# LNA_Testboard.net
KiCad netlist of a schematic drawn in Altium Designer
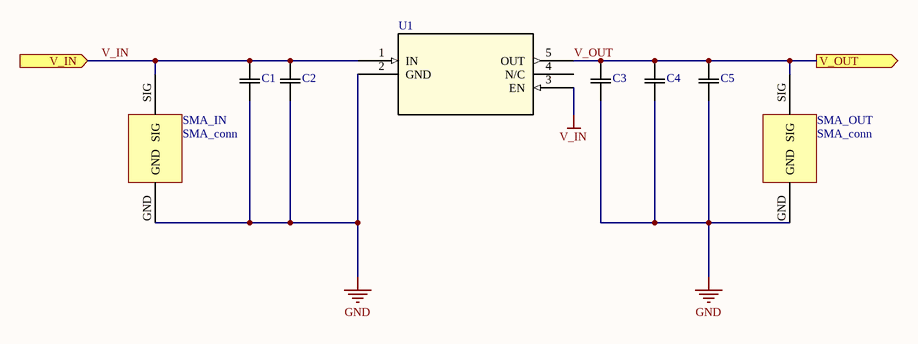
[diagram p0: LNA_Testboard.SchDoc]

(export (version "E")
  (design (tool "Eeschema 10.0.6"))
  (components
    (comp (ref "C1")
      (value "~")
      (footprint "0402Capacitor_Yageo:YAG_CC0402")
      (description "No Description Available")
      (fields
        (field (name "MANUFACTURER_PART_NUMBER") "C0201C270J3GACTU")
        (field (name "COPYRIGHT") "Copyright (C) 2018 Accelerated Designs. All rights reserved")
      )
      (libsource (lib "0201Capacitor_Yageo") (part "C0201C270J3GACTU"))
    )
    (comp (ref "C2")
      (value "~")
      (footprint "0402Capacitor_Yageo:YAG_CC0402")
      (description "No Description Available")
      (fields
        (field (name "MANUFACTURER_PART_NUMBER") "C0201C270J3GACTU")
        (field (name "COPYRIGHT") "Copyright (C) 2018 Accelerated Designs. All rights reserved")
      )
      (libsource (lib "0201Capacitor_Yageo") (part "C0201C270J3GACTU"))
    )
    (comp (ref "C3")
      (value "~")
      (footprint "0402Capacitor_Yageo:YAG_CC0402")
      (description "No Description Available")
      (fields
        (field (name "MANUFACTURER_PART_NUMBER") "C0201C270J3GACTU")
        (field (name "COPYRIGHT") "Copyright (C) 2018 Accelerated Designs. All rights reserved")
      )
      (libsource (lib "0201Capacitor_Yageo") (part "C0201C270J3GACTU"))
    )
    (comp (ref "C4")
      (value "~")
      (footprint "0402Capacitor_Yageo:YAG_CC0402")
      (description "No Description Available")
      (fields
        (field (name "MANUFACTURER_PART_NUMBER") "C0201C270J3GACTU")
        (field (name "COPYRIGHT") "Copyright (C) 2018 Accelerated Designs. All rights reserved")
      )
      (libsource (lib "0201Capacitor_Yageo") (part "C0201C270J3GACTU"))
    )
    (comp (ref "C5")
      (value "~")
      (footprint "0402Capacitor_Yageo:YAG_CC0402")
      (description "No Description Available")
      (fields
        (field (name "MANUFACTURER_PART_NUMBER") "C0201C270J3GACTU")
        (field (name "COPYRIGHT") "Copyright (C) 2018 Accelerated Designs. All rights reserved")
      )
      (libsource (lib "0201Capacitor_Yageo") (part "C0201C270J3GACTU"))
    )
    (comp (ref "SMA_IN")
      (value "SMA_conn")
      (footprint "SMA_conn")
      (libsource (lib "SMA_conn") (part "SMA_conn"))
    )
    (comp (ref "SMA_OUT")
      (value "SMA_conn")
      (footprint "SMA_conn")
      (libsource (lib "SMA_conn") (part "SMA_conn"))
    )
    (comp (ref "U1")
      (value "~")
      (footprint "TI_LDO_3V3_SOT325:DBV5")
      (description "No Description Available")
      (fields
        (field (name "MANUFACTURER_PART_NUMBER") "LP5907MFX-3.3/NOPB")
        (field (name "COPYRIGHT") "Copyright (C) 2018 Accelerated Designs. All rights reserved")
      )
      (libsource (lib "TI_LDO_3V3_SOT325") (part "LP5907MFX-3.3/NO"))
    )
  )
  (nets
    (net (code "1") (name "/V_OUT") (class "Default")
      (node (ref "C3") (pin "1") (pinfunction "1_1") (pintype "passive"))
      (node (ref "C4") (pin "1") (pinfunction "1_1") (pintype "passive"))
      (node (ref "C5") (pin "1") (pinfunction "1_1") (pintype "passive"))
      (node (ref "SMA_OUT") (pin "SIG") (pinfunction "SIG_SIG") (pintype "passive"))
      (node (ref "U1") (pin "5") (pinfunction "OUT_5") (pintype "output"))
    )
    (net (code "2") (name "GND") (class "Default")
      (node (ref "C1") (pin "2") (pinfunction "2_2") (pintype "passive"))
      (node (ref "C2") (pin "2") (pinfunction "2_2") (pintype "passive"))
      (node (ref "C3") (pin "2") (pinfunction "2_2") (pintype "passive"))
      (node (ref "C4") (pin "2") (pinfunction "2_2") (pintype "passive"))
      (node (ref "C5") (pin "2") (pinfunction "2_2") (pintype "passive"))
      (node (ref "SMA_IN") (pin "GND") (pinfunction "GND_GND") (pintype "passive"))
      (node (ref "SMA_OUT") (pin "GND") (pinfunction "GND_GND") (pintype "passive"))
      (node (ref "U1") (pin "2") (pinfunction "GND_2") (pintype "power_in"))
    )
    (net (code "3") (name "V_IN") (class "Default")
      (node (ref "C1") (pin "1") (pinfunction "1_1") (pintype "passive"))
      (node (ref "C2") (pin "1") (pinfunction "1_1") (pintype "passive"))
      (node (ref "SMA_IN") (pin "SIG") (pinfunction "SIG_SIG") (pintype "passive"))
      (node (ref "U1") (pin "1") (pinfunction "IN_1") (pintype "input"))
      (node (ref "U1") (pin "3") (pinfunction "EN_3") (pintype "input"))
    )
    (net (code "4") (name "unconnected-(U1-N{slash}C-Pad4)") (class "Default")
      (node (ref "U1") (pin "4") (pinfunction "N/C_4") (pintype "passive"))
    )
  )
)
